# F1C100s.net
KiCad netlist of a schematic drawn in Altium Designer
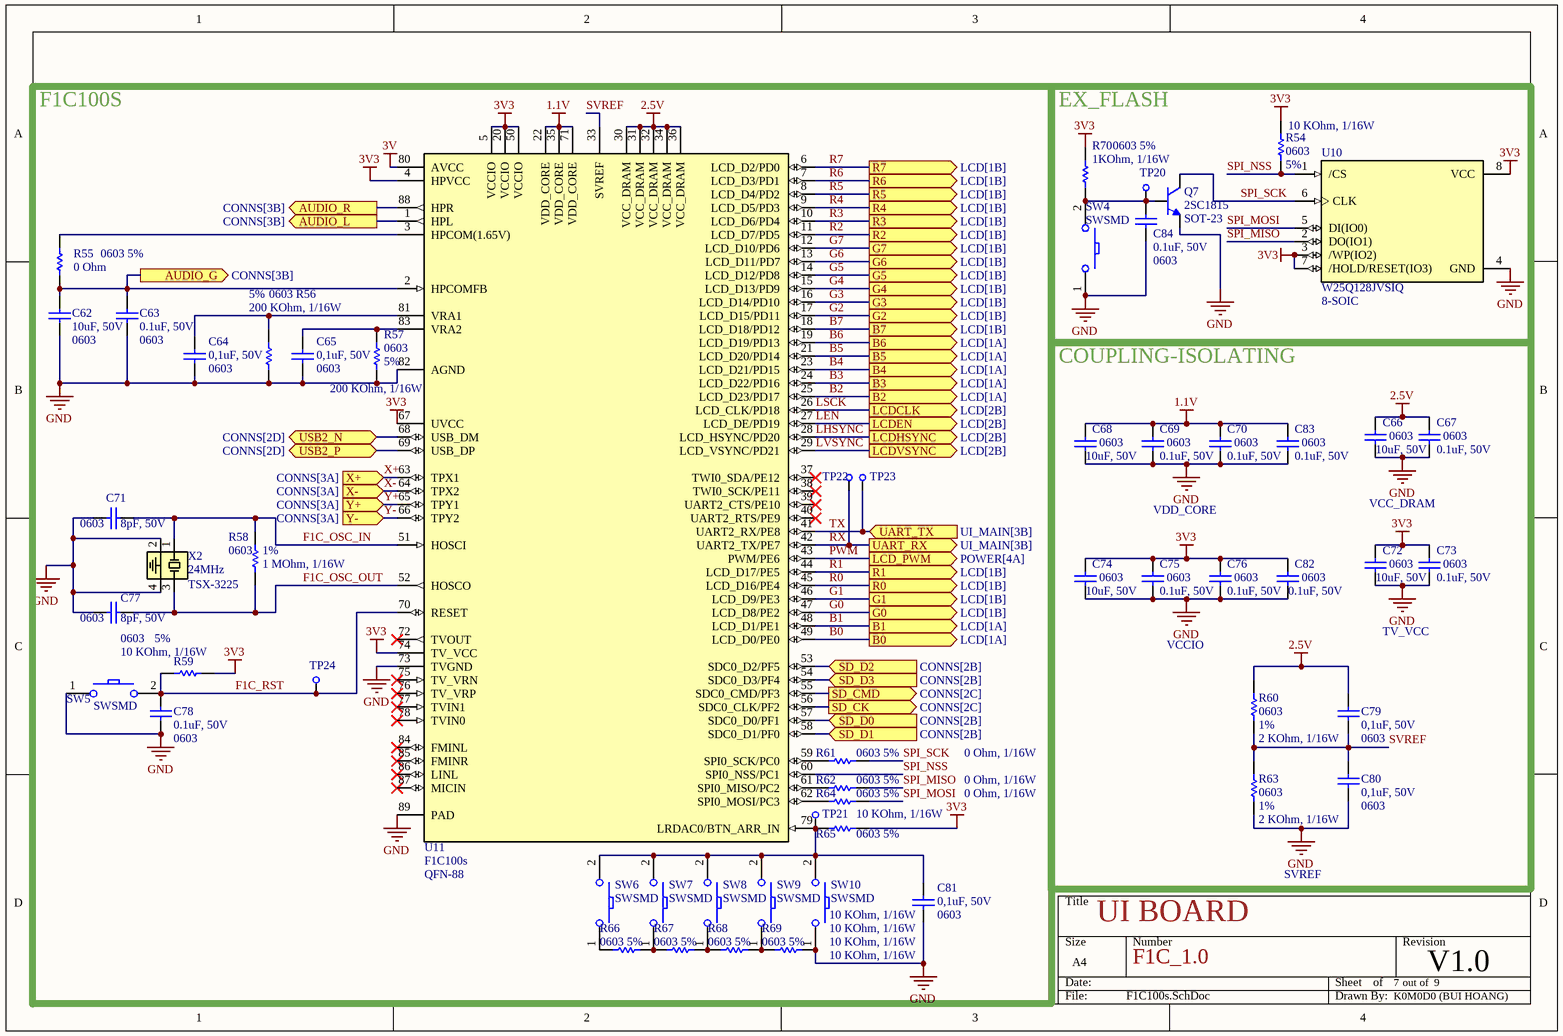
[diagram p0: F1C100s.SchDoc]

(export (version "E")
  (design (tool "Eeschema 10.0.6"))
  (components
    (comp (ref "C62")
      (value "10uF, 50V")
      (footprint "C_0603")
      (description "CAP_0603")
      (fields (field (name "PACKAGE") "0603"))
      (libsource (lib "DisplayLib") (part "CAP_0603"))
    )
    (comp (ref "C63")
      (value "0.1uF, 50V")
      (footprint "C_0603")
      (description "CAP_0603")
      (fields (field (name "PACKAGE") "0603"))
      (libsource (lib "DisplayLib") (part "CAP_0603"))
    )
    (comp (ref "C64")
      (value "0,1uF, 50V")
      (footprint "C_0603")
      (description "CAP_0603")
      (fields (field (name "PACKAGE") "0603"))
      (libsource (lib "DisplayLib") (part "CAP_0603"))
    )
    (comp (ref "C65")
      (value "0,1uF, 50V")
      (footprint "C_0603")
      (description "CAP_0603")
      (fields (field (name "PACKAGE") "0603"))
      (libsource (lib "DisplayLib") (part "CAP_0603"))
    )
    (comp (ref "C66")
      (value "10uF, 50V")
      (footprint "C_0603")
      (description "CAP_0603")
      (fields (field (name "PACKAGE") "0603"))
      (libsource (lib "DisplayLib") (part "CAP_0603"))
    )
    (comp (ref "C67")
      (value "0.1uF, 50V")
      (footprint "C_0603")
      (description "CAP_0603")
      (fields (field (name "PACKAGE") "0603"))
      (libsource (lib "DisplayLib") (part "CAP_0603"))
    )
    (comp (ref "C68")
      (value "10uF, 50V")
      (footprint "C_0603")
      (description "CAP_0603")
      (fields (field (name "PACKAGE") "0603"))
      (libsource (lib "DisplayLib") (part "CAP_0603"))
    )
    (comp (ref "C69")
      (value "0.1uF, 50V")
      (footprint "C_0603")
      (description "CAP_0603")
      (fields (field (name "PACKAGE") "0603"))
      (libsource (lib "DisplayLib") (part "CAP_0603"))
    )
    (comp (ref "C70")
      (value "0.1uF, 50V")
      (footprint "C_0603")
      (description "CAP_0603")
      (fields (field (name "PACKAGE") "0603"))
      (libsource (lib "DisplayLib") (part "CAP_0603"))
    )
    (comp (ref "C71")
      (value "8pF, 50V")
      (footprint "C_0603")
      (description "CAP_0603")
      (fields (field (name "PACKAGE") "0603"))
      (libsource (lib "DisplayLib") (part "CAP_0603"))
    )
    (comp (ref "C72")
      (value "10uF, 50V")
      (footprint "C_0603")
      (description "CAP_0603")
      (fields (field (name "PACKAGE") "0603"))
      (libsource (lib "DisplayLib") (part "CAP_0603"))
    )
    (comp (ref "C73")
      (value "0.1uF, 50V")
      (footprint "C_0603")
      (description "CAP_0603")
      (fields (field (name "PACKAGE") "0603"))
      (libsource (lib "DisplayLib") (part "CAP_0603"))
    )
    (comp (ref "C74")
      (value "10uF, 50V")
      (footprint "C_0603")
      (description "CAP_0603")
      (fields (field (name "PACKAGE") "0603"))
      (libsource (lib "DisplayLib") (part "CAP_0603"))
    )
    (comp (ref "C75")
      (value "0.1uF, 50V")
      (footprint "C_0603")
      (description "CAP_0603")
      (fields (field (name "PACKAGE") "0603"))
      (libsource (lib "DisplayLib") (part "CAP_0603"))
    )
    (comp (ref "C76")
      (value "0.1uF, 50V")
      (footprint "C_0603")
      (description "CAP_0603")
      (fields (field (name "PACKAGE") "0603"))
      (libsource (lib "DisplayLib") (part "CAP_0603"))
    )
    (comp (ref "C77")
      (value "8pF, 50V")
      (footprint "C_0603")
      (description "CAP_0603")
      (fields (field (name "PACKAGE") "0603"))
      (libsource (lib "DisplayLib") (part "CAP_0603"))
    )
    (comp (ref "C78")
      (value "0.1uF, 50V")
      (footprint "C_0603")
      (description "CAP_0603")
      (fields (field (name "PACKAGE") "0603"))
      (libsource (lib "DisplayLib") (part "CAP_0603"))
    )
    (comp (ref "C79")
      (value "0,1uF, 50V")
      (footprint "C_0603")
      (description "CAP_0603")
      (fields (field (name "PACKAGE") "0603"))
      (libsource (lib "DisplayLib") (part "CAP_0603"))
    )
    (comp (ref "C80")
      (value "0,1uF, 50V")
      (footprint "C_0603")
      (description "CAP_0603")
      (fields (field (name "PACKAGE") "0603"))
      (libsource (lib "DisplayLib") (part "CAP_0603"))
    )
    (comp (ref "C81")
      (value "0,1uF, 50V")
      (footprint "C_0603")
      (description "CAP_0603")
      (fields (field (name "PACKAGE") "0603"))
      (libsource (lib "DisplayLib") (part "CAP_0603"))
    )
    (comp (ref "C82")
      (value "0.1uF, 50V")
      (footprint "C_0603")
      (description "CAP_0603")
      (fields (field (name "PACKAGE") "0603"))
      (libsource (lib "DisplayLib") (part "CAP_0603"))
    )
    (comp (ref "C83")
      (value "0.1uF, 50V")
      (footprint "C_0603")
      (description "CAP_0603")
      (fields (field (name "PACKAGE") "0603"))
      (libsource (lib "DisplayLib") (part "CAP_0603"))
    )
    (comp (ref "C84")
      (value "0.1uF, 50V")
      (footprint "C_0603")
      (description "CAP_0603")
      (fields (field (name "PACKAGE") "0603"))
      (libsource (lib "DisplayLib") (part "CAP_0603"))
    )
    (comp (ref "Q7")
      (value "2SC1815")
      (footprint "PKG_SOT-23")
      (description "HF Transistor NPN")
      (fields (field (name "PACKAGE") "SOT-23"))
      (libsource (lib "DisplayLib") (part "2SC1815"))
    )
    (comp (ref "R54")
      (value "10 KOhm, 1/16W")
      (footprint "R_0603")
      (description "RES_0603")
      (fields (field (name "PACKAGE") "0603") (field (name "ACC") "5%"))
      (libsource (lib "DisplayLib") (part "RES_0603"))
    )
    (comp (ref "R55")
      (value "0 Ohm")
      (footprint "R_0603")
      (description "RES_0603")
      (fields (field (name "PACKAGE") "0603") (field (name "ACC") "5%"))
      (libsource (lib "DisplayLib") (part "RES_0603"))
    )
    (comp (ref "R56")
      (value "200 KOhm, 1/16W")
      (footprint "R_0603")
      (description "RES_0603")
      (fields (field (name "PACKAGE") "0603") (field (name "ACC") "5%"))
      (libsource (lib "DisplayLib") (part "RES_0603"))
    )
    (comp (ref "R57")
      (value "200 KOhm, 1/16W")
      (footprint "R_0603")
      (description "RES_0603")
      (fields (field (name "PACKAGE") "0603") (field (name "ACC") "5%"))
      (libsource (lib "DisplayLib") (part "RES_0603"))
    )
    (comp (ref "R58")
      (value "1 MOhm, 1/16W")
      (footprint "R_0603")
      (description "RES_0603")
      (fields (field (name "PACKAGE") "0603") (field (name "ACC") "1%"))
      (libsource (lib "DisplayLib") (part "RES_0603"))
    )
    (comp (ref "R59")
      (value "10 KOhm, 1/16W")
      (footprint "R_0603")
      (description "RES_0603")
      (fields (field (name "PACKAGE") "0603") (field (name "ACC") "5%"))
      (libsource (lib "DisplayLib") (part "RES_0603"))
    )
    (comp (ref "R60")
      (value "2 KOhm, 1/16W")
      (footprint "R_0603")
      (description "RES_0603")
      (fields (field (name "PACKAGE") "0603") (field (name "ACC") "1%"))
      (libsource (lib "DisplayLib") (part "RES_0603"))
    )
    (comp (ref "R61")
      (value "0 Ohm, 1/16W")
      (footprint "R_0603")
      (description "RES_0603")
      (fields (field (name "PACKAGE") "0603") (field (name "ACC") "5%"))
      (libsource (lib "DisplayLib") (part "RES_0603"))
    )
    (comp (ref "R62")
      (value "0 Ohm, 1/16W")
      (footprint "R_0603")
      (description "RES_0603")
      (fields (field (name "PACKAGE") "0603") (field (name "ACC") "5%"))
      (libsource (lib "DisplayLib") (part "RES_0603"))
    )
    (comp (ref "R63")
      (value "2 KOhm, 1/16W")
      (footprint "R_0603")
      (description "RES_0603")
      (fields (field (name "PACKAGE") "0603") (field (name "ACC") "1%"))
      (libsource (lib "DisplayLib") (part "RES_0603"))
    )
    (comp (ref "R64")
      (value "0 Ohm, 1/16W")
      (footprint "R_0603")
      (description "RES_0603")
      (fields (field (name "PACKAGE") "0603") (field (name "ACC") "5%"))
      (libsource (lib "DisplayLib") (part "RES_0603"))
    )
    (comp (ref "R65")
      (value "10 KOhm, 1/16W")
      (footprint "R_0603")
      (description "RES_0603")
      (fields (field (name "PACKAGE") "0603") (field (name "ACC") "5%"))
      (libsource (lib "DisplayLib") (part "RES_0603"))
    )
    (comp (ref "R66")
      (value "10 KOhm, 1/16W")
      (footprint "R_0603")
      (description "RES_0603")
      (fields (field (name "PACKAGE") "0603") (field (name "ACC") "5%"))
      (libsource (lib "DisplayLib") (part "RES_0603"))
    )
    (comp (ref "R67")
      (value "10 KOhm, 1/16W")
      (footprint "R_0603")
      (description "RES_0603")
      (fields (field (name "PACKAGE") "0603") (field (name "ACC") "5%"))
      (libsource (lib "DisplayLib") (part "RES_0603"))
    )
    (comp (ref "R68")
      (value "10 KOhm, 1/16W")
      (footprint "R_0603")
      (description "RES_0603")
      (fields (field (name "PACKAGE") "0603") (field (name "ACC") "5%"))
      (libsource (lib "DisplayLib") (part "RES_0603"))
    )
    (comp (ref "R69")
      (value "10 KOhm, 1/16W")
      (footprint "R_0603")
      (description "RES_0603")
      (fields (field (name "PACKAGE") "0603") (field (name "ACC") "5%"))
      (libsource (lib "DisplayLib") (part "RES_0603"))
    )
    (comp (ref "R70")
      (value "1KOhm, 1/16W")
      (footprint "R_0603")
      (description "RES_0603")
      (fields (field (name "PACKAGE") "0603") (field (name "ACC") "5%"))
      (libsource (lib "DisplayLib") (part "RES_0603"))
    )
    (comp (ref "SW4")
      (value "SWSMD")
      (footprint "SW_SMD_NOGND")
      (description "SW_SMD")
      (libsource (lib "") (part "SWSMD_NOGND_1"))
    )
    (comp (ref "SW5")
      (value "SWSMD")
      (footprint "SW_SMD_NOGND")
      (description "SW_SMD")
      (libsource (lib "DisplayLib") (part "SWSMD_NOGND"))
    )
    (comp (ref "SW6")
      (value "SWSMD")
      (footprint "SW_SMD_NOGND")
      (description "SW_SMD")
      (libsource (lib "") (part "SWSMD_NOGND_1"))
    )
    (comp (ref "SW7")
      (value "SWSMD")
      (footprint "SW_SMD_NOGND")
      (description "SW_SMD")
      (libsource (lib "") (part "SWSMD_NOGND_1"))
    )
    (comp (ref "SW8")
      (value "SWSMD")
      (footprint "SW_SMD_NOGND")
      (description "SW_SMD")
      (libsource (lib "") (part "SWSMD_NOGND_1"))
    )
    (comp (ref "SW9")
      (value "SWSMD")
      (footprint "SW_SMD_NOGND")
      (description "SW_SMD")
      (libsource (lib "") (part "SWSMD_NOGND_1"))
    )
    (comp (ref "SW10")
      (value "SWSMD")
      (footprint "SW_SMD_NOGND")
      (description "SW_SMD")
      (libsource (lib "") (part "SWSMD_NOGND_1"))
    )
    (comp (ref "TP20")
      (value "TESTPT")
      (footprint "TESTPT")
      (description "Test point")
      (libsource (lib "DisplayLib") (part "TESTPT"))
    )
    (comp (ref "TP21")
      (value "TESTPT")
      (footprint "TESTPT")
      (description "Test point")
      (libsource (lib "DisplayLib") (part "TESTPT"))
    )
    (comp (ref "TP22")
      (value "TESTPT")
      (footprint "TESTPT")
      (description "Test point")
      (libsource (lib "DisplayLib") (part "TESTPT"))
    )
    (comp (ref "TP23")
      (value "TESTPT")
      (footprint "TESTPT")
      (description "Test point")
      (libsource (lib "DisplayLib") (part "TESTPT"))
    )
    (comp (ref "TP24")
      (value "TESTPT")
      (footprint "TESTPT")
      (description "Test point")
      (libsource (lib "DisplayLib") (part "TESTPT"))
    )
    (comp (ref "U10")
      (value "W25Q128JVSIQ")
      (footprint "PKG_8-SOIC")
      (description "FLASH - NOR Memory IC 128Mb (16M x 8) SPI - Quad I/O, QPI, DTR 133 MHz 8-SOIC")
      (fields (field (name "PACKAGE") "8-SOIC"))
      (libsource (lib "DisplayLib") (part "W25Q128JVSIQ"))
    )
    (comp (ref "U11")
      (value "F1C100s")
      (footprint "PKG_QFN-88")
      (fields (field (name "PACKAGE") "QFN-88"))
      (libsource (lib "DisplayLib") (part "F1C100s"))
    )
    (comp (ref "X2")
      (value "24MHz")
      (footprint "PKG_TSX-3225")
      (description "Crystal, 24 MHz, -30 to 85 degC, 3.2 x 2.5 x 0.9 mm SMD")
      (fields (field (name "PACKAGE") "TSX-3225"))
      (libsource (lib "DisplayLib") (part "XTAL"))
    )
  )
  (nets
    (net (code "1") (name "/AUDIO_G") (class "Default")
      (node (ref "C62") (pin "2") (pinfunction "2_2") (pintype "passive"))
      (node (ref "C63") (pin "2") (pinfunction "2_2") (pintype "passive"))
      (node (ref "R55") (pin "1") (pinfunction "1_1") (pintype "passive"))
      (node (ref "U11") (pin "2") (pinfunction "HPCOMFB_2") (pintype "input"))
    )
    (net (code "2") (name "/AUDIO_L") (class "Default")
      (node (ref "U11") (pin "1") (pinfunction "HPL_1") (pintype "output"))
    )
    (net (code "3") (name "/AUDIO_R") (class "Default")
      (node (ref "U11") (pin "88") (pinfunction "HPR_88") (pintype "output"))
    )
    (net (code "4") (name "/B0") (class "Default")
      (node (ref "U11") (pin "49") (pinfunction "LCD_D0/PE0_49") (pintype "bidirectional"))
    )
    (net (code "5") (name "/B1") (class "Default")
      (node (ref "U11") (pin "48") (pinfunction "LCD_D1/PE1_48") (pintype "bidirectional"))
    )
    (net (code "6") (name "/B2") (class "Default")
      (node (ref "U11") (pin "25") (pinfunction "LCD_D23/PD17_25") (pintype "bidirectional"))
    )
    (net (code "7") (name "/B3") (class "Default")
      (node (ref "U11") (pin "24") (pinfunction "LCD_D22/PD16_24") (pintype "bidirectional"))
    )
    (net (code "8") (name "/B4") (class "Default")
      (node (ref "U11") (pin "23") (pinfunction "LCD_D21/PD15_23") (pintype "bidirectional"))
    )
    (net (code "9") (name "/B5") (class "Default")
      (node (ref "U11") (pin "21") (pinfunction "LCD_D20/PD14_21") (pintype "bidirectional"))
    )
    (net (code "10") (name "/B6") (class "Default")
      (node (ref "U11") (pin "19") (pinfunction "LCD_D19/PD13_19") (pintype "bidirectional"))
    )
    (net (code "11") (name "/B7") (class "Default")
      (node (ref "U11") (pin "18") (pinfunction "LCD_D18/PD12_18") (pintype "bidirectional"))
    )
    (net (code "12") (name "/F1C_OSC_IN") (class "Default")
      (node (ref "C71") (pin "2") (pinfunction "2_2") (pintype "passive"))
      (node (ref "R58") (pin "2") (pinfunction "2_2") (pintype "passive"))
      (node (ref "U11") (pin "51") (pinfunction "HOSCI_51") (pintype "input"))
      (node (ref "X2") (pin "1") (pinfunction "1_1") (pintype "passive"))
    )
    (net (code "13") (name "/F1C_OSC_OUT") (class "Default")
      (node (ref "C77") (pin "2") (pinfunction "2_2") (pintype "passive"))
      (node (ref "R58") (pin "1") (pinfunction "1_1") (pintype "passive"))
      (node (ref "U11") (pin "52") (pinfunction "HOSCO_52") (pintype "output"))
      (node (ref "X2") (pin "3") (pinfunction "3_3") (pintype "passive"))
    )
    (net (code "14") (name "/F1C_RST") (class "Default")
      (node (ref "C78") (pin "2") (pinfunction "2_2") (pintype "passive"))
      (node (ref "R59") (pin "1") (pinfunction "1_1") (pintype "passive"))
      (node (ref "SW5") (pin "2") (pinfunction "2_2") (pintype "passive"))
      (node (ref "TP24") (pin "1") (pinfunction "1_1") (pintype "passive"))
      (node (ref "U11") (pin "70") (pinfunction "RESET_70") (pintype "bidirectional"))
    )
    (net (code "15") (name "/G0") (class "Default")
      (node (ref "U11") (pin "47") (pinfunction "LCD_D8/PE2_47") (pintype "bidirectional"))
    )
    (net (code "16") (name "/G1") (class "Default")
      (node (ref "U11") (pin "46") (pinfunction "LCD_D9/PE3_46") (pintype "bidirectional"))
    )
    (net (code "17") (name "/G2") (class "Default")
      (node (ref "U11") (pin "17") (pinfunction "LCD_D15/PD11_17") (pintype "bidirectional"))
    )
    (net (code "18") (name "/G3") (class "Default")
      (node (ref "U11") (pin "16") (pinfunction "LCD_D14/PD10_16") (pintype "bidirectional"))
    )
    (net (code "19") (name "/G4") (class "Default")
      (node (ref "U11") (pin "15") (pinfunction "LCD_D13/PD9_15") (pintype "bidirectional"))
    )
    (net (code "20") (name "/G5") (class "Default")
      (node (ref "U11") (pin "14") (pinfunction "LCD_D12/PD8_14") (pintype "bidirectional"))
    )
    (net (code "21") (name "/G6") (class "Default")
      (node (ref "U11") (pin "13") (pinfunction "LCD_D11/PD7_13") (pintype "bidirectional"))
    )
    (net (code "22") (name "/G7") (class "Default")
      (node (ref "U11") (pin "12") (pinfunction "LCD_D10/PD6_12") (pintype "bidirectional"))
    )
    (net (code "23") (name "/LEN") (class "Default")
      (node (ref "U11") (pin "27") (pinfunction "LCD_DE/PD19_27") (pintype "bidirectional"))
    )
    (net (code "24") (name "/LHSYNC") (class "Default")
      (node (ref "U11") (pin "28") (pinfunction "LCD_HSYNC/PD20_28") (pintype "bidirectional"))
    )
    (net (code "25") (name "/LSCK") (class "Default")
      (node (ref "U11") (pin "26") (pinfunction "LCD_CLK/PD18_26") (pintype "bidirectional"))
    )
    (net (code "26") (name "/LVSYNC") (class "Default")
      (node (ref "U11") (pin "29") (pinfunction "LCD_VSYNC/PD21_29") (pintype "bidirectional"))
    )
    (net (code "27") (name "/PWM") (class "Default")
      (node (ref "U11") (pin "43") (pinfunction "PWM/PE6_43") (pintype "bidirectional"))
    )
    (net (code "28") (name "/R0") (class "Default")
      (node (ref "U11") (pin "45") (pinfunction "LCD_D16/PE4_45") (pintype "bidirectional"))
    )
    (net (code "29") (name "/R1") (class "Default")
      (node (ref "U11") (pin "44") (pinfunction "LCD_D17/PE5_44") (pintype "bidirectional"))
    )
    (net (code "30") (name "/R2") (class "Default")
      (node (ref "U11") (pin "11") (pinfunction "LCD_D7/PD5_11") (pintype "bidirectional"))
    )
    (net (code "31") (name "/R3") (class "Default")
      (node (ref "U11") (pin "10") (pinfunction "LCD_D6/PD4_10") (pintype "bidirectional"))
    )
    (net (code "32") (name "/R4") (class "Default")
      (node (ref "U11") (pin "9") (pinfunction "LCD_D5/PD3_9") (pintype "bidirectional"))
    )
    (net (code "33") (name "/R5") (class "Default")
      (node (ref "U11") (pin "8") (pinfunction "LCD_D4/PD2_8") (pintype "bidirectional"))
    )
    (net (code "34") (name "/R6") (class "Default")
      (node (ref "U11") (pin "7") (pinfunction "LCD_D3/PD1_7") (pintype "bidirectional"))
    )
    (net (code "35") (name "/R7") (class "Default")
      (node (ref "U11") (pin "6") (pinfunction "LCD_D2/PD0_6") (pintype "bidirectional"))
    )
    (net (code "36") (name "/RX") (class "Default")
      (node (ref "TP22") (pin "1") (pinfunction "1_1") (pintype "passive"))
      (node (ref "U11") (pin "42") (pinfunction "UART2_TX/PE7_42") (pintype "bidirectional"))
    )
    (net (code "37") (name "/SD_CK") (class "Default")
      (node (ref "U11") (pin "56") (pinfunction "SDC0_CLK/PF2_56") (pintype "bidirectional"))
    )
    (net (code "38") (name "/SD_CMD") (class "Default")
      (node (ref "U11") (pin "55") (pinfunction "SDC0_CMD/PF3_55") (pintype "bidirectional"))
    )
    (net (code "39") (name "/SD_D0") (class "Default")
      (node (ref "U11") (pin "57") (pinfunction "SDC0_D0/PF1_57") (pintype "bidirectional"))
    )
    (net (code "40") (name "/SD_D1") (class "Default")
      (node (ref "U11") (pin "58") (pinfunction "SDC0_D1/PF0_58") (pintype "bidirectional"))
    )
    (net (code "41") (name "/SD_D2") (class "Default")
      (node (ref "U11") (pin "53") (pinfunction "SDC0_D2/PF5_53") (pintype "bidirectional"))
    )
    (net (code "42") (name "/SD_D3") (class "Default")
      (node (ref "U11") (pin "54") (pinfunction "SDC0_D3/PF4_54") (pintype "bidirectional"))
    )
    (net (code "43") (name "/SPI_MISO") (class "Default")
      (node (ref "R62") (pin "1") (pinfunction "1_1") (pintype "passive"))
      (node (ref "U10") (pin "2") (pinfunction "DO(IO1)_2") (pintype "bidirectional"))
    )
    (net (code "44") (name "/SPI_MOSI") (class "Default")
      (node (ref "R64") (pin "1") (pinfunction "1_1") (pintype "passive"))
      (node (ref "U10") (pin "5") (pinfunction "DI(IO0)_5") (pintype "bidirectional"))
    )
    (net (code "45") (name "/SPI_NSS") (class "Default")
      (node (ref "R54") (pin "1") (pinfunction "1_1") (pintype "passive"))
      (node (ref "U10") (pin "1") (pinfunction "/CS_1") (pintype "input"))
      (node (ref "U11") (pin "60") (pinfunction "SPI0_NSS/PC1_60") (pintype "bidirectional"))
    )
    (net (code "46") (name "/SPI_SCK") (class "Default")
      (node (ref "Q7") (pin "3") (pinfunction "C_3") (pintype "passive"))
      (node (ref "R61") (pin "1") (pinfunction "1_1") (pintype "passive"))
      (node (ref "U10") (pin "6") (pinfunction "CLK_6") (pintype "input"))
    )
    (net (code "47") (name "/SVREF") (class "Default")
      (node (ref "C79") (pin "1") (pinfunction "1_1") (pintype "passive"))
      (node (ref "C80") (pin "2") (pinfunction "2_2") (pintype "passive"))
      (node (ref "R60") (pin "1") (pinfunction "1_1") (pintype "passive"))
      (node (ref "R63") (pin "2") (pinfunction "2_2") (pintype "passive"))
      (node (ref "U11") (pin "33") (pinfunction "SVREF_33") (pintype "power_in"))
    )
    (net (code "48") (name "/TX") (class "Default")
      (node (ref "TP23") (pin "1") (pinfunction "1_1") (pintype "passive"))
      (node (ref "U11") (pin "41") (pinfunction "UART2_RX/PE8_41") (pintype "bidirectional"))
    )
    (net (code "49") (name "/USB2_N") (class "Default")
      (node (ref "U11") (pin "68") (pinfunction "USB_DM_68") (pintype "bidirectional"))
    )
    (net (code "50") (name "/USB2_P") (class "Default")
      (node (ref "U11") (pin "69") (pinfunction "USB_DP_69") (pintype "bidirectional"))
    )
    (net (code "51") (name "/X+") (class "Default")
      (node (ref "U11") (pin "63") (pinfunction "TPX1_63") (pintype "bidirectional"))
    )
    (net (code "52") (name "/X-") (class "Default")
      (node (ref "U11") (pin "64") (pinfunction "TPX2_64") (pintype "bidirectional"))
    )
    (net (code "53") (name "/Y+") (class "Default")
      (node (ref "U11") (pin "65") (pinfunction "TPY1_65") (pintype "bidirectional"))
    )
    (net (code "54") (name "/Y-") (class "Default")
      (node (ref "U11") (pin "66") (pinfunction "TPY2_66") (pintype "bidirectional"))
    )
    (net (code "55") (name "1.1V") (class "Default")
      (node (ref "C68") (pin "2") (pinfunction "2_2") (pintype "passive"))
      (node (ref "C69") (pin "2") (pinfunction "2_2") (pintype "passive"))
      (node (ref "C70") (pin "2") (pinfunction "2_2") (pintype "passive"))
      (node (ref "C83") (pin "2") (pinfunction "2_2") (pintype "passive"))
      (node (ref "U11") (pin "22") (pinfunction "VDD_CORE_22") (pintype "power_in"))
      (node (ref "U11") (pin "35") (pinfunction "VDD_CORE_35") (pintype "power_in"))
      (node (ref "U11") (pin "71") (pinfunction "VDD_CORE_71") (pintype "power_in"))
    )
    (net (code "56") (name "2.5V") (class "Default")
      (node (ref "C66") (pin "2") (pinfunction "2_2") (pintype "passive"))
      (node (ref "C67") (pin "2") (pinfunction "2_2") (pintype "passive"))
      (node (ref "C79") (pin "2") (pinfunction "2_2") (pintype "passive"))
      (node (ref "R60") (pin "2") (pinfunction "2_2") (pintype "passive"))
      (node (ref "U11") (pin "30") (pinfunction "VCC_DRAM_30") (pintype "power_in"))
      (node (ref "U11") (pin "31") (pinfunction "VCC_DRAM_31") (pintype "power_in"))
      (node (ref "U11") (pin "32") (pinfunction "VCC_DRAM_32") (pintype "power_in"))
      (node (ref "U11") (pin "34") (pinfunction "VCC_DRAM_34") (pintype "power_in"))
      (node (ref "U11") (pin "36") (pinfunction "VCC_DRAM_36") (pintype "power_in"))
    )
    (net (code "57") (name "3V") (class "Default")
      (node (ref "U11") (pin "80") (pinfunction "AVCC_80") (pintype "power_in"))
    )
    (net (code "58") (name "3V3") (class "Default")
      (node (ref "C72") (pin "2") (pinfunction "2_2") (pintype "passive"))
      (node (ref "C73") (pin "2") (pinfunction "2_2") (pintype "passive"))
      (node (ref "C74") (pin "2") (pinfunction "2_2") (pintype "passive"))
      (node (ref "C75") (pin "2") (pinfunction "2_2") (pintype "passive"))
      (node (ref "C76") (pin "2") (pinfunction "2_2") (pintype "passive"))
      (node (ref "C82") (pin "2") (pinfunction "2_2") (pintype "passive"))
      (node (ref "R54") (pin "2") (pinfunction "2_2") (pintype "passive"))
      (node (ref "R59") (pin "2") (pinfunction "2_2") (pintype "passive"))
      (node (ref "R65") (pin "2") (pinfunction "2_2") (pintype "passive"))
      (node (ref "R70") (pin "2") (pinfunction "2_2") (pintype "passive"))
      (node (ref "U10") (pin "3") (pinfunction "/WP(IO2)_3") (pintype "bidirectional"))
      (node (ref "U10") (pin "7") (pinfunction "/HOLD/RESET(IO3)_7") (pintype "bidirectional"))
      (node (ref "U10") (pin "8") (pinfunction "VCC_8") (pintype "power_in"))
      (node (ref "U11") (pin "20") (pinfunction "VCCIO_20") (pintype "power_in"))
      (node (ref "U11") (pin "4") (pinfunction "HPVCC_4") (pintype "power_in"))
      (node (ref "U11") (pin "5") (pinfunction "VCCIO_5") (pintype "power_in"))
      (node (ref "U11") (pin "50") (pinfunction "VCCIO_50") (pintype "power_in"))
      (node (ref "U11") (pin "67") (pinfunction "UVCC_67") (pintype "power_in"))
      (node (ref "U11") (pin "74") (pinfunction "TV_VCC_74") (pintype "power_in"))
    )
    (net (code "59") (name "GND") (class "Default")
      (node (ref "C62") (pin "1") (pinfunction "1_1") (pintype "passive"))
      (node (ref "C63") (pin "1") (pinfunction "1_1") (pintype "passive"))
      (node (ref "C64") (pin "1") (pinfunction "1_1") (pintype "passive"))
      (node (ref "C65") (pin "1") (pinfunction "1_1") (pintype "passive"))
      (node (ref "C66") (pin "1") (pinfunction "1_1") (pintype "passive"))
      (node (ref "C67") (pin "1") (pinfunction "1_1") (pintype "passive"))
      (node (ref "C68") (pin "1") (pinfunction "1_1") (pintype "passive"))
      (node (ref "C69") (pin "1") (pinfunction "1_1") (pintype "passive"))
      (node (ref "C70") (pin "1") (pinfunction "1_1") (pintype "passive"))
      (node (ref "C71") (pin "1") (pinfunction "1_1") (pintype "passive"))
      (node (ref "C72") (pin "1") (pinfunction "1_1") (pintype "passive"))
      (node (ref "C73") (pin "1") (pinfunction "1_1") (pintype "passive"))
      (node (ref "C74") (pin "1") (pinfunction "1_1") (pintype "passive"))
      (node (ref "C75") (pin "1") (pinfunction "1_1") (pintype "passive"))
      (node (ref "C76") (pin "1") (pinfunction "1_1") (pintype "passive"))
      (node (ref "C77") (pin "1") (pinfunction "1_1") (pintype "passive"))
      (node (ref "C78") (pin "1") (pinfunction "1_1") (pintype "passive"))
      (node (ref "C80") (pin "1") (pinfunction "1_1") (pintype "passive"))
      (node (ref "C81") (pin "1") (pinfunction "1_1") (pintype "passive"))
      (node (ref "C82") (pin "1") (pinfunction "1_1") (pintype "passive"))
      (node (ref "C83") (pin "1") (pinfunction "1_1") (pintype "passive"))
      (node (ref "C84") (pin "1") (pinfunction "1_1") (pintype "passive"))
      (node (ref "Q7") (pin "2") (pinfunction "E_2") (pintype "passive"))
      (node (ref "R56") (pin "1") (pinfunction "1_1") (pintype "passive"))
      (node (ref "R57") (pin "1") (pinfunction "1_1") (pintype "passive"))
      (node (ref "R63") (pin "1") (pinfunction "1_1") (pintype "passive"))
      (node (ref "R69") (pin "2") (pinfunction "2_2") (pintype "passive"))
      (node (ref "SW10") (pin "1") (pinfunction "1_1") (pintype "passive"))
      (node (ref "SW4") (pin "1") (pinfunction "1_1") (pintype "passive"))
      (node (ref "SW5") (pin "1") (pinfunction "1_1") (pintype "passive"))
      (node (ref "U10") (pin "4") (pinfunction "GND_4") (pintype "power_in"))
      (node (ref "U11") (pin "73") (pinfunction "TVGND_73") (pintype "power_in"))
      (node (ref "U11") (pin "82") (pinfunction "AGND_82") (pintype "power_in"))
      (node (ref "U11") (pin "89") (pinfunction "PAD_89") (pintype "passive"))
      (node (ref "X2") (pin "2") (pinfunction "2_2") (pintype "passive"))
      (node (ref "X2") (pin "4") (pinfunction "4_4") (pintype "passive"))
    )
    (net (code "60") (name "Net-(Q7-B)") (class "Default")
      (node (ref "C84") (pin "2") (pinfunction "2_2") (pintype "passive"))
      (node (ref "Q7") (pin "1") (pinfunction "B_1") (pintype "passive"))
      (node (ref "R70") (pin "1") (pinfunction "1_1") (pintype "passive"))
      (node (ref "SW4") (pin "2") (pinfunction "2_2") (pintype "passive"))
      (node (ref "TP20") (pin "1") (pinfunction "1_1") (pintype "passive"))
    )
    (net (code "61") (name "Net-(R66-Pad1)") (class "Default")
      (node (ref "R66") (pin "1") (pinfunction "1_1") (pintype "passive"))
      (node (ref "SW6") (pin "1") (pinfunction "1_1") (pintype "passive"))
    )
    (net (code "62") (name "Net-(R66-Pad2)") (class "Default")
      (node (ref "R66") (pin "2") (pinfunction "2_2") (pintype "passive"))
      (node (ref "R67") (pin "1") (pinfunction "1_1") (pintype "passive"))
      (node (ref "SW7") (pin "1") (pinfunction "1_1") (pintype "passive"))
    )
    (net (code "63") (name "Net-(R67-Pad2)") (class "Default")
      (node (ref "R67") (pin "2") (pinfunction "2_2") (pintype "passive"))
      (node (ref "R68") (pin "1") (pinfunction "1_1") (pintype "passive"))
      (node (ref "SW8") (pin "1") (pinfunction "1_1") (pintype "passive"))
    )
    (net (code "64") (name "Net-(R68-Pad2)") (class "Default")
      (node (ref "R68") (pin "2") (pinfunction "2_2") (pintype "passive"))
      (node (ref "R69") (pin "1") (pinfunction "1_1") (pintype "passive"))
      (node (ref "SW9") (pin "1") (pinfunction "1_1") (pintype "passive"))
    )
    (net (code "65") (name "Net-(U11-HPCOM(1.65V))") (class "Default")
      (node (ref "R55") (pin "2") (pinfunction "2_2") (pintype "passive"))
      (node (ref "U11") (pin "3") (pinfunction "HPCOM(1.65V)_3") (pintype "power_in"))
    )
    (net (code "66") (name "Net-(U11-LRDAC0{slash}BTN_ARR_IN)") (class "Default")
      (node (ref "C81") (pin "2") (pinfunction "2_2") (pintype "passive"))
      (node (ref "R65") (pin "1") (pinfunction "1_1") (pintype "passive"))
      (node (ref "SW10") (pin "2") (pinfunction "2_2") (pintype "passive"))
      (node (ref "SW6") (pin "2") (pinfunction "2_2") (pintype "passive"))
      (node (ref "SW7") (pin "2") (pinfunction "2_2") (pintype "passive"))
      (node (ref "SW8") (pin "2") (pinfunction "2_2") (pintype "passive"))
      (node (ref "SW9") (pin "2") (pinfunction "2_2") (pintype "passive"))
      (node (ref "TP21") (pin "1") (pinfunction "1_1") (pintype "passive"))
      (node (ref "U11") (pin "79") (pinfunction "LRDAC0/BTN_ARR_IN_79") (pintype "input"))
    )
    (net (code "67") (name "Net-(U11-SPI0_MISO{slash}PC2)") (class "Default")
      (node (ref "R62") (pin "2") (pinfunction "2_2") (pintype "passive"))
      (node (ref "U11") (pin "61") (pinfunction "SPI0_MISO/PC2_61") (pintype "bidirectional"))
    )
    (net (code "68") (name "Net-(U11-SPI0_MOSI{slash}PC3)") (class "Default")
      (node (ref "R64") (pin "2") (pinfunction "2_2") (pintype "passive"))
      (node (ref "U11") (pin "62") (pinfunction "SPI0_MOSI/PC3_62") (pintype "bidirectional"))
    )
    (net (code "69") (name "Net-(U11-SPI0_SCK{slash}PC0)") (class "Default")
      (node (ref "R61") (pin "2") (pinfunction "2_2") (pintype "passive"))
      (node (ref "U11") (pin "59") (pinfunction "SPI0_SCK/PC0_59") (pintype "bidirectional"))
    )
    (net (code "70") (name "Net-(U11-VRA1)") (class "Default")
      (node (ref "C64") (pin "2") (pinfunction "2_2") (pintype "passive"))
      (node (ref "R56") (pin "2") (pinfunction "2_2") (pintype "passive"))
      (node (ref "U11") (pin "81") (pinfunction "VRA1_81") (pintype "passive"))
    )
    (net (code "71") (name "Net-(U11-VRA2)") (class "Default")
      (node (ref "C65") (pin "2") (pinfunction "2_2") (pintype "passive"))
      (node (ref "R57") (pin "2") (pinfunction "2_2") (pintype "passive"))
      (node (ref "U11") (pin "83") (pinfunction "VRA2_83") (pintype "passive"))
    )
    (net (code "72") (name "unconnected-(U11-FMINL-Pad84)") (class "Default")
      (node (ref "U11") (pin "84") (pinfunction "FMINL_84") (pintype "bidirectional+no_connect"))
    )
    (net (code "73") (name "unconnected-(U11-FMINR-Pad85)") (class "Default")
      (node (ref "U11") (pin "85") (pinfunction "FMINR_85") (pintype "bidirectional+no_connect"))
    )
    (net (code "74") (name "unconnected-(U11-LINL-Pad86)") (class "Default")
      (node (ref "U11") (pin "86") (pinfunction "LINL_86") (pintype "bidirectional+no_connect"))
    )
    (net (code "75") (name "unconnected-(U11-MICIN-Pad87)") (class "Default")
      (node (ref "U11") (pin "87") (pinfunction "MICIN_87") (pintype "bidirectional+no_connect"))
    )
    (net (code "76") (name "unconnected-(U11-TVIN0-Pad78)") (class "Default")
      (node (ref "U11") (pin "78") (pinfunction "TVIN0_78") (pintype "input+no_connect"))
    )
    (net (code "77") (name "unconnected-(U11-TVIN1-Pad77)") (class "Default")
      (node (ref "U11") (pin "77") (pinfunction "TVIN1_77") (pintype "input+no_connect"))
    )
    (net (code "78") (name "unconnected-(U11-TVOUT-Pad72)") (class "Default")
      (node (ref "U11") (pin "72") (pinfunction "TVOUT_72") (pintype "output+no_connect"))
    )
    (net (code "79") (name "unconnected-(U11-TV_VRN-Pad75)") (class "Default")
      (node (ref "U11") (pin "75") (pinfunction "TV_VRN_75") (pintype "input+no_connect"))
    )
    (net (code "80") (name "unconnected-(U11-TV_VRP-Pad76)") (class "Default")
      (node (ref "U11") (pin "76") (pinfunction "TV_VRP_76") (pintype "input+no_connect"))
    )
    (net (code "81") (name "unconnected-(U11-TWI0_SCK{slash}PE11-Pad38)") (class "Default")
      (node (ref "U11") (pin "38") (pinfunction "TWI0_SCK/PE11_38") (pintype "bidirectional+no_connect"))
    )
    (net (code "82") (name "unconnected-(U11-TWI0_SDA{slash}PE12-Pad37)") (class "Default")
      (node (ref "U11") (pin "37") (pinfunction "TWI0_SDA/PE12_37") (pintype "bidirectional+no_connect"))
    )
    (net (code "83") (name "unconnected-(U11-UART2_CTS{slash}PE10-Pad39)") (class "Default")
      (node (ref "U11") (pin "39") (pinfunction "UART2_CTS/PE10_39") (pintype "bidirectional+no_connect"))
    )
    (net (code "84") (name "unconnected-(U11-UART2_RTS{slash}PE9-Pad40)") (class "Default")
      (node (ref "U11") (pin "40") (pinfunction "UART2_RTS/PE9_40") (pintype "bidirectional+no_connect"))
    )
  )
)
